# rocket_main_micro.net
KiCad netlist of a schematic drawn in Altium Designer
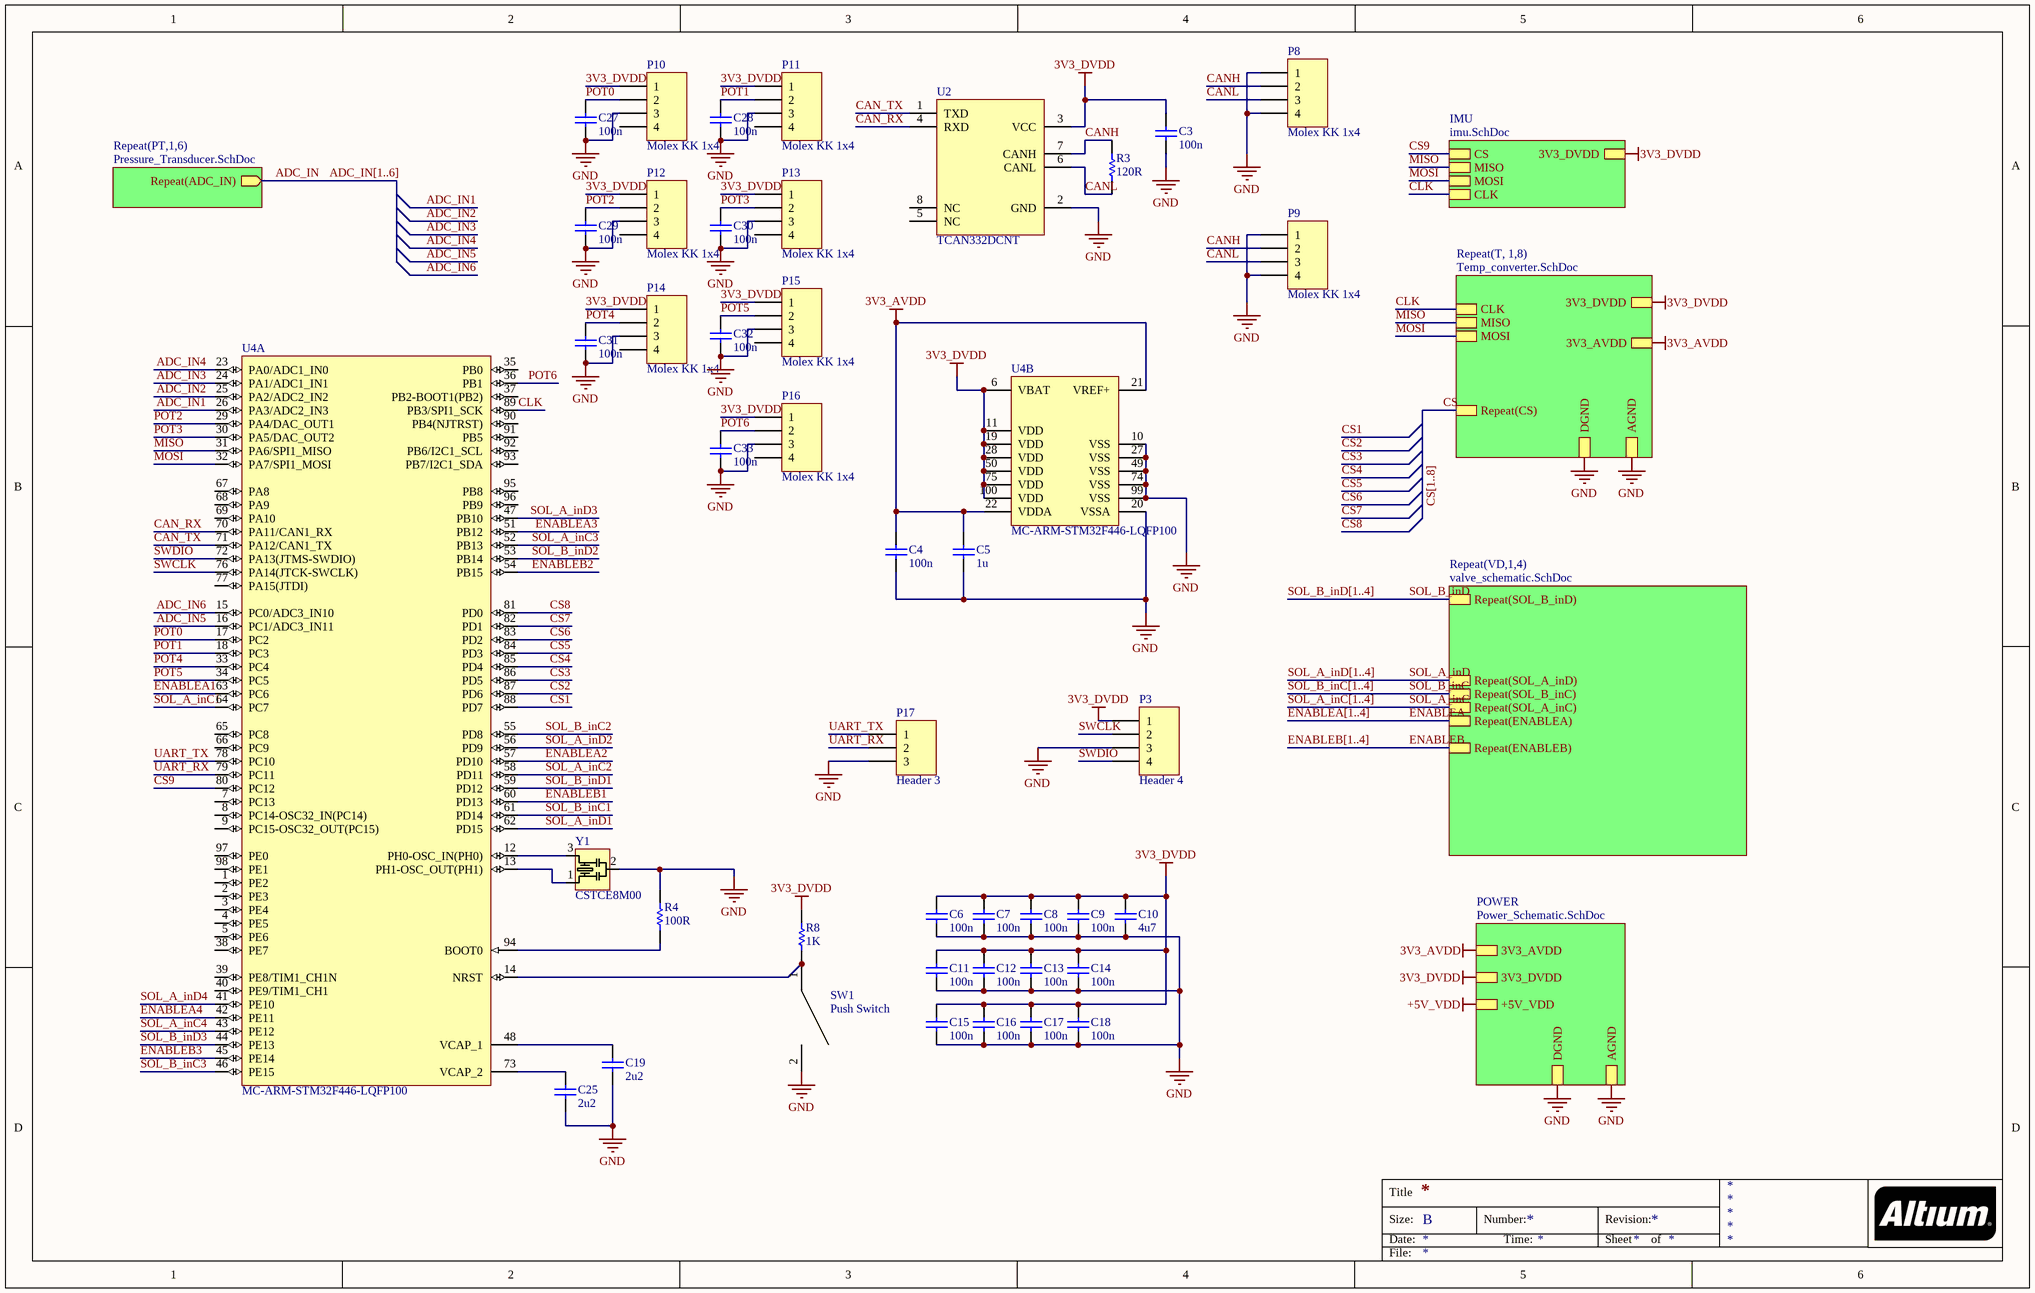
[diagram p0: rocket_main_micro.SchDoc]

(export (version "E")
  (design (tool "Eeschema 10.0.6"))
  (components
    (comp (ref "C3")
      (value "100n")
      (footprint "C0805")
      (description "0805 Capacitor")
      (libsource (lib "PARSEC") (part "C0805"))
    )
    (comp (ref "C4")
      (value "100n")
      (footprint "C0805")
      (description "0805 Capacitor")
      (libsource (lib "PARSEC1") (part "C0805"))
    )
    (comp (ref "C5")
      (value "1u")
      (footprint "C0805")
      (description "0805 Capacitor")
      (libsource (lib "PARSEC1") (part "C0805"))
    )
    (comp (ref "C6")
      (value "100n")
      (footprint "C0805")
      (description "0805 Capacitor")
      (libsource (lib "PARSEC1") (part "C0805"))
    )
    (comp (ref "C7")
      (value "100n")
      (footprint "C0805")
      (description "0805 Capacitor")
      (libsource (lib "PARSEC1") (part "C0805"))
    )
    (comp (ref "C8")
      (value "100n")
      (footprint "C0805")
      (description "0805 Capacitor")
      (libsource (lib "PARSEC1") (part "C0805"))
    )
    (comp (ref "C9")
      (value "100n")
      (footprint "C0805")
      (description "0805 Capacitor")
      (libsource (lib "PARSEC1") (part "C0805"))
    )
    (comp (ref "C10")
      (value "4u7")
      (footprint "C0805")
      (description "0805 Capacitor")
      (libsource (lib "PARSEC1") (part "C0805"))
    )
    (comp (ref "C11")
      (value "100n")
      (footprint "C0805")
      (description "0805 Capacitor")
      (libsource (lib "PARSEC1") (part "C0805"))
    )
    (comp (ref "C12")
      (value "100n")
      (footprint "C0805")
      (description "0805 Capacitor")
      (libsource (lib "PARSEC1") (part "C0805"))
    )
    (comp (ref "C13")
      (value "100n")
      (footprint "C0805")
      (description "0805 Capacitor")
      (libsource (lib "PARSEC1") (part "C0805"))
    )
    (comp (ref "C14")
      (value "100n")
      (footprint "C0805")
      (description "0805 Capacitor")
      (libsource (lib "PARSEC1") (part "C0805"))
    )
    (comp (ref "C15")
      (value "100n")
      (footprint "C0805")
      (description "0805 Capacitor")
      (libsource (lib "PARSEC1") (part "C0805"))
    )
    (comp (ref "C16")
      (value "100n")
      (footprint "C0805")
      (description "0805 Capacitor")
      (libsource (lib "PARSEC1") (part "C0805"))
    )
    (comp (ref "C17")
      (value "100n")
      (footprint "C0805")
      (description "0805 Capacitor")
      (libsource (lib "PARSEC1") (part "C0805"))
    )
    (comp (ref "C18")
      (value "100n")
      (footprint "C0805")
      (description "0805 Capacitor")
      (libsource (lib "PARSEC1") (part "C0805"))
    )
    (comp (ref "C19")
      (value "2u2")
      (footprint "C0805")
      (description "0805 Capacitor")
      (libsource (lib "PARSEC1") (part "C0805"))
    )
    (comp (ref "C25")
      (value "2u2")
      (footprint "C0805")
      (description "0805 Capacitor")
      (libsource (lib "PARSEC1") (part "C0805"))
    )
    (comp (ref "C27")
      (value "100n")
      (footprint "C0805")
      (description "0805 Capacitor")
      (libsource (lib "PARSEC1") (part "C0805"))
    )
    (comp (ref "C28")
      (value "100n")
      (footprint "C0805")
      (description "0805 Capacitor")
      (libsource (lib "PARSEC1") (part "C0805"))
    )
    (comp (ref "C29")
      (value "100n")
      (footprint "C0805")
      (description "0805 Capacitor")
      (libsource (lib "PARSEC1") (part "C0805"))
    )
    (comp (ref "C30")
      (value "100n")
      (footprint "C0805")
      (description "0805 Capacitor")
      (libsource (lib "PARSEC1") (part "C0805"))
    )
    (comp (ref "C31")
      (value "100n")
      (footprint "C0805")
      (description "0805 Capacitor")
      (libsource (lib "PARSEC1") (part "C0805"))
    )
    (comp (ref "C32")
      (value "100n")
      (footprint "C0805")
      (description "0805 Capacitor")
      (libsource (lib "PARSEC1") (part "C0805"))
    )
    (comp (ref "C33")
      (value "100n")
      (footprint "C0805")
      (description "0805 Capacitor")
      (libsource (lib "PARSEC1") (part "C0805"))
    )
    (comp (ref "P3")
      (value "Header 4")
      (footprint "HDR1X4")
      (description "Header, 4-Pin")
      (fields (field (name "PUBLISHER") "Altium Limited"))
      (libsource (lib "Miscellaneous Connectors") (part "Header 4"))
    )
    (comp (ref "P8")
      (value "Molex KK 1x4")
      (footprint "Molex KK 4x1")
      (description "1x4 Molex KK Connector")
      (libsource (lib "PARSEC") (part "Molex KK 1x4"))
    )
    (comp (ref "P9")
      (value "Molex KK 1x4")
      (footprint "Molex KK 4x1")
      (description "1x4 Molex KK Connector")
      (libsource (lib "PARSEC") (part "Molex KK 1x4"))
    )
    (comp (ref "P10")
      (value "Molex KK 1x4")
      (footprint "Molex KK 4x1")
      (description "1x4 Molex KK Connector")
      (libsource (lib "PARSEC") (part "Molex KK 1x4"))
    )
    (comp (ref "P11")
      (value "Molex KK 1x4")
      (footprint "Molex KK 4x1")
      (description "1x4 Molex KK Connector")
      (libsource (lib "PARSEC") (part "Molex KK 1x4"))
    )
    (comp (ref "P12")
      (value "Molex KK 1x4")
      (footprint "Molex KK 4x1")
      (description "1x4 Molex KK Connector")
      (libsource (lib "PARSEC") (part "Molex KK 1x4"))
    )
    (comp (ref "P13")
      (value "Molex KK 1x4")
      (footprint "Molex KK 4x1")
      (description "1x4 Molex KK Connector")
      (libsource (lib "PARSEC") (part "Molex KK 1x4"))
    )
    (comp (ref "P14")
      (value "Molex KK 1x4")
      (footprint "Molex KK 4x1")
      (description "1x4 Molex KK Connector")
      (libsource (lib "PARSEC") (part "Molex KK 1x4"))
    )
    (comp (ref "P15")
      (value "Molex KK 1x4")
      (footprint "Molex KK 4x1")
      (description "1x4 Molex KK Connector")
      (libsource (lib "PARSEC") (part "Molex KK 1x4"))
    )
    (comp (ref "P16")
      (value "Molex KK 1x4")
      (footprint "Molex KK 4x1")
      (description "1x4 Molex KK Connector")
      (libsource (lib "PARSEC") (part "Molex KK 1x4"))
    )
    (comp (ref "P17")
      (value "Header 3")
      (footprint "HDR1X3")
      (description "Header, 3-Pin")
      (fields (field (name "PUBLISHER") "Altium Limited"))
      (libsource (lib "Miscellaneous Connectors") (part "Header 3"))
    )
    (comp (ref "R3")
      (value "120R")
      (footprint "R0805")
      (description "RESISTOR 0805")
      (libsource (lib "PARSEC") (part "R0805"))
    )
    (comp (ref "R4")
      (value "100R")
      (footprint "R0805")
      (description "RESISTOR 0805")
      (libsource (lib "PARSEC1") (part "R0805"))
    )
    (comp (ref "R8")
      (value "1K")
      (footprint "R0805")
      (description "RESISTOR 0805")
      (libsource (lib "PARSEC1") (part "R0805"))
    )
    (comp (ref "SW1")
      (value "Push Switch")
      (footprint "PUSHBUTTON")
      (libsource (lib "PARSEC") (part "PUSHBUTTON"))
    )
    (comp (ref "U2")
      (value "TCAN332DCNT")
      (footprint "SOT-23-8")
      (description "IC TXRX CAN 3.3V SOT23-8")
      (libsource (lib "PARSEC") (part "TCAN332DCNT"))
    )
    (comp (ref "U4")
      (value "MC-ARM-STM32F446-LQFP100")
      (footprint "STM-LQFP100_N")
      (libsource (lib "PARSEC1") (part "MC-ARM-STM32F446-LQFP100"))
    )
    (comp (ref "Y1")
      (value "CSTCE8M00")
      (footprint "8MHz Ceramic Resonator")
      (description "8MHz Ceramic Resonator")
      (libsource (lib "PARSEC1") (part "CSTCE8M00"))
    )
  )
  (nets
    (net (code "6") (name "/ADC_IN1") (class "Default")
      (node (ref "U4") (pin "26") (pinfunction "PA3/ADC2_IN3_26") (pintype "bidirectional"))
    )
    (net (code "7") (name "/ADC_IN2") (class "Default")
      (node (ref "U4") (pin "25") (pinfunction "PA2/ADC2_IN2_25") (pintype "bidirectional"))
    )
    (net (code "8") (name "/ADC_IN3") (class "Default")
      (node (ref "U4") (pin "24") (pinfunction "PA1/ADC1_IN1_24") (pintype "bidirectional"))
    )
    (net (code "9") (name "/ADC_IN4") (class "Default")
      (node (ref "U4") (pin "23") (pinfunction "PA0/ADC1_IN0_23") (pintype "bidirectional"))
    )
    (net (code "10") (name "/ADC_IN5") (class "Default")
      (node (ref "U4") (pin "16") (pinfunction "PC1/ADC3_IN11_16") (pintype "bidirectional"))
    )
    (net (code "11") (name "/ADC_IN6") (class "Default")
      (node (ref "U4") (pin "15") (pinfunction "PC0/ADC3_IN10_15") (pintype "bidirectional"))
    )
    (net (code "13") (name "/CANH") (class "Default")
      (node (ref "P8") (pin "2") (pinfunction "2_2") (pintype "passive"))
      (node (ref "P9") (pin "2") (pinfunction "2_2") (pintype "passive"))
      (node (ref "R3") (pin "2") (pinfunction "2_2") (pintype "passive"))
      (node (ref "U2") (pin "7") (pinfunction "CANH_7") (pintype "passive"))
    )
    (net (code "14") (name "/CANL") (class "Default")
      (node (ref "P8") (pin "3") (pinfunction "3_3") (pintype "passive"))
      (node (ref "P9") (pin "3") (pinfunction "3_3") (pintype "passive"))
      (node (ref "R3") (pin "1") (pinfunction "1_1") (pintype "passive"))
      (node (ref "U2") (pin "6") (pinfunction "CANL_6") (pintype "passive"))
    )
    (net (code "15") (name "/CAN_RX") (class "Default")
      (node (ref "U2") (pin "4") (pinfunction "RXD_4") (pintype "passive"))
      (node (ref "U4") (pin "70") (pinfunction "PA11/CAN1_RX_70") (pintype "bidirectional"))
    )
    (net (code "16") (name "/CAN_TX") (class "Default")
      (node (ref "U2") (pin "1") (pinfunction "TXD_1") (pintype "passive"))
      (node (ref "U4") (pin "71") (pinfunction "PA12/CAN1_TX_71") (pintype "bidirectional"))
    )
    (net (code "17") (name "/CLK") (class "Default")
      (node (ref "U4") (pin "89") (pinfunction "PB3/SPI1_SCK_89") (pintype "bidirectional"))
    )
    (net (code "18") (name "/CS1") (class "Default")
      (node (ref "U4") (pin "88") (pinfunction "PD7_88") (pintype "bidirectional"))
    )
    (net (code "19") (name "/CS2") (class "Default")
      (node (ref "U4") (pin "87") (pinfunction "PD6_87") (pintype "bidirectional"))
    )
    (net (code "20") (name "/CS3") (class "Default")
      (node (ref "U4") (pin "86") (pinfunction "PD5_86") (pintype "bidirectional"))
    )
    (net (code "21") (name "/CS4") (class "Default")
      (node (ref "U4") (pin "85") (pinfunction "PD4_85") (pintype "bidirectional"))
    )
    (net (code "22") (name "/CS5") (class "Default")
      (node (ref "U4") (pin "84") (pinfunction "PD3_84") (pintype "bidirectional"))
    )
    (net (code "23") (name "/CS6") (class "Default")
      (node (ref "U4") (pin "83") (pinfunction "PD2_83") (pintype "bidirectional"))
    )
    (net (code "24") (name "/CS7") (class "Default")
      (node (ref "U4") (pin "82") (pinfunction "PD1_82") (pintype "bidirectional"))
    )
    (net (code "25") (name "/CS8") (class "Default")
      (node (ref "U4") (pin "81") (pinfunction "PD0_81") (pintype "bidirectional"))
    )
    (net (code "26") (name "/CS9") (class "Default")
      (node (ref "U4") (pin "80") (pinfunction "PC12_80") (pintype "bidirectional"))
    )
    (net (code "29") (name "/ENABLEA1") (class "Default")
      (node (ref "U4") (pin "63") (pinfunction "PC6_63") (pintype "bidirectional"))
    )
    (net (code "30") (name "/ENABLEA2") (class "Default")
      (node (ref "U4") (pin "57") (pinfunction "PD10_57") (pintype "bidirectional"))
    )
    (net (code "31") (name "/ENABLEA3") (class "Default")
      (node (ref "U4") (pin "51") (pinfunction "PB12_51") (pintype "bidirectional"))
    )
    (net (code "32") (name "/ENABLEA4") (class "Default")
      (node (ref "U4") (pin "42") (pinfunction "PE11_42") (pintype "bidirectional"))
    )
    (net (code "35") (name "/ENABLEB1") (class "Default")
      (node (ref "U4") (pin "60") (pinfunction "PD13_60") (pintype "bidirectional"))
    )
    (net (code "36") (name "/ENABLEB2") (class "Default")
      (node (ref "U4") (pin "54") (pinfunction "PB15_54") (pintype "bidirectional"))
    )
    (net (code "37") (name "/ENABLEB3") (class "Default")
      (node (ref "U4") (pin "45") (pinfunction "PE14_45") (pintype "bidirectional"))
    )
    (net (code "39") (name "/MISO") (class "Default")
      (node (ref "U4") (pin "31") (pinfunction "PA6/SPI1_MISO_31") (pintype "bidirectional"))
    )
    (net (code "40") (name "/MOSI") (class "Default")
      (node (ref "U4") (pin "32") (pinfunction "PA7/SPI1_MOSI_32") (pintype "bidirectional"))
    )
    (net (code "41") (name "/POT0") (class "Default")
      (node (ref "C27") (pin "1") (pinfunction "1_1") (pintype "passive"))
      (node (ref "P10") (pin "2") (pinfunction "2_2") (pintype "passive"))
      (node (ref "U4") (pin "17") (pinfunction "PC2_17") (pintype "bidirectional"))
    )
    (net (code "42") (name "/POT1") (class "Default")
      (node (ref "C28") (pin "1") (pinfunction "1_1") (pintype "passive"))
      (node (ref "P11") (pin "2") (pinfunction "2_2") (pintype "passive"))
      (node (ref "U4") (pin "18") (pinfunction "PC3_18") (pintype "bidirectional"))
    )
    (net (code "43") (name "/POT2") (class "Default")
      (node (ref "C29") (pin "1") (pinfunction "1_1") (pintype "passive"))
      (node (ref "P12") (pin "2") (pinfunction "2_2") (pintype "passive"))
      (node (ref "U4") (pin "29") (pinfunction "PA4/DAC_OUT1_29") (pintype "bidirectional"))
    )
    (net (code "44") (name "/POT3") (class "Default")
      (node (ref "C30") (pin "1") (pinfunction "1_1") (pintype "passive"))
      (node (ref "P13") (pin "2") (pinfunction "2_2") (pintype "passive"))
      (node (ref "U4") (pin "30") (pinfunction "PA5/DAC_OUT2_30") (pintype "bidirectional"))
    )
    (net (code "45") (name "/POT4") (class "Default")
      (node (ref "C31") (pin "1") (pinfunction "1_1") (pintype "passive"))
      (node (ref "P14") (pin "2") (pinfunction "2_2") (pintype "passive"))
      (node (ref "U4") (pin "33") (pinfunction "PC4_33") (pintype "bidirectional"))
    )
    (net (code "46") (name "/POT5") (class "Default")
      (node (ref "C32") (pin "1") (pinfunction "1_1") (pintype "passive"))
      (node (ref "P15") (pin "2") (pinfunction "2_2") (pintype "passive"))
      (node (ref "U4") (pin "34") (pinfunction "PC5_34") (pintype "bidirectional"))
    )
    (net (code "47") (name "/POT6") (class "Default")
      (node (ref "C33") (pin "1") (pinfunction "1_1") (pintype "passive"))
      (node (ref "P16") (pin "2") (pinfunction "2_2") (pintype "passive"))
      (node (ref "U4") (pin "36") (pinfunction "PB1_36") (pintype "bidirectional"))
    )
    (net (code "49") (name "/SOL_A_inC1") (class "Default")
      (node (ref "U4") (pin "64") (pinfunction "PC7_64") (pintype "bidirectional"))
    )
    (net (code "50") (name "/SOL_A_inC2") (class "Default")
      (node (ref "U4") (pin "58") (pinfunction "PD11_58") (pintype "bidirectional"))
    )
    (net (code "51") (name "/SOL_A_inC3") (class "Default")
      (node (ref "U4") (pin "52") (pinfunction "PB13_52") (pintype "bidirectional"))
    )
    (net (code "52") (name "/SOL_A_inC4") (class "Default")
      (node (ref "U4") (pin "43") (pinfunction "PE12_43") (pintype "bidirectional"))
    )
    (net (code "55") (name "/SOL_A_inD1") (class "Default")
      (node (ref "U4") (pin "62") (pinfunction "PD15_62") (pintype "bidirectional"))
    )
    (net (code "56") (name "/SOL_A_inD2") (class "Default")
      (node (ref "U4") (pin "56") (pinfunction "PD9_56") (pintype "bidirectional"))
    )
    (net (code "57") (name "/SOL_A_inD3") (class "Default")
      (node (ref "U4") (pin "47") (pinfunction "PB10_47") (pintype "bidirectional"))
    )
    (net (code "58") (name "/SOL_A_inD4") (class "Default")
      (node (ref "U4") (pin "41") (pinfunction "PE10_41") (pintype "bidirectional"))
    )
    (net (code "61") (name "/SOL_B_inC1") (class "Default")
      (node (ref "U4") (pin "61") (pinfunction "PD14_61") (pintype "bidirectional"))
    )
    (net (code "62") (name "/SOL_B_inC2") (class "Default")
      (node (ref "U4") (pin "55") (pinfunction "PD8_55") (pintype "bidirectional"))
    )
    (net (code "63") (name "/SOL_B_inC3") (class "Default")
      (node (ref "U4") (pin "46") (pinfunction "PE15_46") (pintype "bidirectional"))
    )
    (net (code "66") (name "/SOL_B_inD1") (class "Default")
      (node (ref "U4") (pin "59") (pinfunction "PD12_59") (pintype "bidirectional"))
    )
    (net (code "67") (name "/SOL_B_inD2") (class "Default")
      (node (ref "U4") (pin "53") (pinfunction "PB14_53") (pintype "bidirectional"))
    )
    (net (code "68") (name "/SOL_B_inD3") (class "Default")
      (node (ref "U4") (pin "44") (pinfunction "PE13_44") (pintype "bidirectional"))
    )
    (net (code "70") (name "/SWCLK") (class "Default")
      (node (ref "P3") (pin "2") (pinfunction "2_2") (pintype "passive"))
      (node (ref "U4") (pin "76") (pinfunction "PA14(JTCK-SWCLK)_76") (pintype "bidirectional"))
    )
    (net (code "71") (name "/SWDIO") (class "Default")
      (node (ref "P3") (pin "4") (pinfunction "4_4") (pintype "passive"))
      (node (ref "U4") (pin "72") (pinfunction "PA13(JTMS-SWDIO)_72") (pintype "bidirectional"))
    )
    (net (code "72") (name "/UART_RX") (class "Default")
      (node (ref "P17") (pin "2") (pinfunction "2_2") (pintype "passive"))
      (node (ref "U4") (pin "79") (pinfunction "PC11_79") (pintype "bidirectional"))
    )
    (net (code "73") (name "/UART_TX") (class "Default")
      (node (ref "P17") (pin "1") (pinfunction "1_1") (pintype "passive"))
      (node (ref "U4") (pin "78") (pinfunction "PC10_78") (pintype "bidirectional"))
    )
    (net (code "74") (name "3V3_AVDD") (class "Default")
      (node (ref "C4") (pin "1") (pinfunction "1_1") (pintype "passive"))
      (node (ref "C5") (pin "1") (pinfunction "1_1") (pintype "passive"))
      (node (ref "U4") (pin "21") (pinfunction "VREF+_21") (pintype "power_in"))
      (node (ref "U4") (pin "22") (pinfunction "VDDA_22") (pintype "power_in"))
    )
    (net (code "75") (name "3V3_DVDD") (class "Default")
      (node (ref "C10") (pin "1") (pinfunction "1_1") (pintype "passive"))
      (node (ref "C11") (pin "1") (pinfunction "1_1") (pintype "passive"))
      (node (ref "C12") (pin "1") (pinfunction "1_1") (pintype "passive"))
      (node (ref "C13") (pin "1") (pinfunction "1_1") (pintype "passive"))
      (node (ref "C14") (pin "1") (pinfunction "1_1") (pintype "passive"))
      (node (ref "C15") (pin "1") (pinfunction "1_1") (pintype "passive"))
      (node (ref "C16") (pin "1") (pinfunction "1_1") (pintype "passive"))
      (node (ref "C17") (pin "1") (pinfunction "1_1") (pintype "passive"))
      (node (ref "C18") (pin "1") (pinfunction "1_1") (pintype "passive"))
      (node (ref "C3") (pin "1") (pinfunction "1_1") (pintype "passive"))
      (node (ref "C6") (pin "1") (pinfunction "1_1") (pintype "passive"))
      (node (ref "C7") (pin "1") (pinfunction "1_1") (pintype "passive"))
      (node (ref "C8") (pin "1") (pinfunction "1_1") (pintype "passive"))
      (node (ref "C9") (pin "1") (pinfunction "1_1") (pintype "passive"))
      (node (ref "P10") (pin "1") (pinfunction "1_1") (pintype "passive"))
      (node (ref "P11") (pin "1") (pinfunction "1_1") (pintype "passive"))
      (node (ref "P12") (pin "1") (pinfunction "1_1") (pintype "passive"))
      (node (ref "P13") (pin "1") (pinfunction "1_1") (pintype "passive"))
      (node (ref "P14") (pin "1") (pinfunction "1_1") (pintype "passive"))
      (node (ref "P15") (pin "1") (pinfunction "1_1") (pintype "passive"))
      (node (ref "P16") (pin "1") (pinfunction "1_1") (pintype "passive"))
      (node (ref "P3") (pin "1") (pinfunction "1_1") (pintype "passive"))
      (node (ref "R8") (pin "2") (pinfunction "2_2") (pintype "passive"))
      (node (ref "U2") (pin "3") (pinfunction "VCC_3") (pintype "passive"))
      (node (ref "U4") (pin "100") (pinfunction "VDD_100") (pintype "power_in"))
      (node (ref "U4") (pin "11") (pinfunction "VDD_11") (pintype "power_in"))
      (node (ref "U4") (pin "19") (pinfunction "VDD_19") (pintype "power_in"))
      (node (ref "U4") (pin "28") (pinfunction "VDD_28") (pintype "power_in"))
      (node (ref "U4") (pin "50") (pinfunction "VDD_50") (pintype "power_in"))
      (node (ref "U4") (pin "6") (pinfunction "VBAT_6") (pintype "power_in"))
      (node (ref "U4") (pin "75") (pinfunction "VDD_75") (pintype "power_in"))
    )
    (net (code "76") (name "GND") (class "Default")
      (node (ref "C10") (pin "2") (pinfunction "2_2") (pintype "passive"))
      (node (ref "C11") (pin "2") (pinfunction "2_2") (pintype "passive"))
      (node (ref "C12") (pin "2") (pinfunction "2_2") (pintype "passive"))
      (node (ref "C13") (pin "2") (pinfunction "2_2") (pintype "passive"))
      (node (ref "C14") (pin "2") (pinfunction "2_2") (pintype "passive"))
      (node (ref "C15") (pin "2") (pinfunction "2_2") (pintype "passive"))
      (node (ref "C16") (pin "2") (pinfunction "2_2") (pintype "passive"))
      (node (ref "C17") (pin "2") (pinfunction "2_2") (pintype "passive"))
      (node (ref "C18") (pin "2") (pinfunction "2_2") (pintype "passive"))
      (node (ref "C19") (pin "2") (pinfunction "2_2") (pintype "passive"))
      (node (ref "C25") (pin "2") (pinfunction "2_2") (pintype "passive"))
      (node (ref "C27") (pin "2") (pinfunction "2_2") (pintype "passive"))
      (node (ref "C28") (pin "2") (pinfunction "2_2") (pintype "passive"))
      (node (ref "C29") (pin "2") (pinfunction "2_2") (pintype "passive"))
      (node (ref "C3") (pin "2") (pinfunction "2_2") (pintype "passive"))
      (node (ref "C30") (pin "2") (pinfunction "2_2") (pintype "passive"))
      (node (ref "C31") (pin "2") (pinfunction "2_2") (pintype "passive"))
      (node (ref "C32") (pin "2") (pinfunction "2_2") (pintype "passive"))
      (node (ref "C33") (pin "2") (pinfunction "2_2") (pintype "passive"))
      (node (ref "C4") (pin "2") (pinfunction "2_2") (pintype "passive"))
      (node (ref "C5") (pin "2") (pinfunction "2_2") (pintype "passive"))
      (node (ref "C6") (pin "2") (pinfunction "2_2") (pintype "passive"))
      (node (ref "C7") (pin "2") (pinfunction "2_2") (pintype "passive"))
      (node (ref "C8") (pin "2") (pinfunction "2_2") (pintype "passive"))
      (node (ref "C9") (pin "2") (pinfunction "2_2") (pintype "passive"))
      (node (ref "P10") (pin "3") (pinfunction "3_3") (pintype "passive"))
      (node (ref "P11") (pin "3") (pinfunction "3_3") (pintype "passive"))
      (node (ref "P12") (pin "3") (pinfunction "3_3") (pintype "passive"))
      (node (ref "P13") (pin "3") (pinfunction "3_3") (pintype "passive"))
      (node (ref "P14") (pin "3") (pinfunction "3_3") (pintype "passive"))
      (node (ref "P15") (pin "3") (pinfunction "3_3") (pintype "passive"))
      (node (ref "P16") (pin "3") (pinfunction "3_3") (pintype "passive"))
      (node (ref "P17") (pin "3") (pinfunction "3_3") (pintype "passive"))
      (node (ref "P3") (pin "3") (pinfunction "3_3") (pintype "passive"))
      (node (ref "P8") (pin "1") (pinfunction "1_1") (pintype "passive"))
      (node (ref "P8") (pin "4") (pinfunction "4_4") (pintype "passive"))
      (node (ref "P9") (pin "1") (pinfunction "1_1") (pintype "passive"))
      (node (ref "P9") (pin "4") (pinfunction "4_4") (pintype "passive"))
      (node (ref "R4") (pin "2") (pinfunction "2_2") (pintype "passive"))
      (node (ref "SW1") (pin "2") (pinfunction "3_2") (pintype "passive"))
      (node (ref "U2") (pin "2") (pinfunction "GND_2") (pintype "passive"))
      (node (ref "U4") (pin "10") (pinfunction "VSS_10") (pintype "power_in"))
      (node (ref "U4") (pin "20") (pinfunction "VSSA_20") (pintype "power_in"))
      (node (ref "U4") (pin "27") (pinfunction "VSS_27") (pintype "power_in"))
      (node (ref "U4") (pin "49") (pinfunction "VSS_49") (pintype "power_in"))
      (node (ref "U4") (pin "74") (pinfunction "VSS_74") (pintype "power_in"))
      (node (ref "U4") (pin "99") (pinfunction "VSS_99") (pintype "power_in"))
      (node (ref "Y1") (pin "2") (pinfunction "GND_2") (pintype "passive"))
    )
    (net (code "77") (name "Net-(SW1-2)") (class "Default")
      (node (ref "R8") (pin "1") (pinfunction "1_1") (pintype "passive"))
      (node (ref "SW1") (pin "1") (pinfunction "2_1") (pintype "passive"))
      (node (ref "U4") (pin "14") (pinfunction "NRST_14") (pintype "bidirectional"))
    )
    (net (code "78") (name "Net-(U4A-BOOT0)") (class "Default")
      (node (ref "R4") (pin "1") (pinfunction "1_1") (pintype "passive"))
      (node (ref "U4") (pin "94") (pinfunction "BOOT0_94") (pintype "input"))
    )
    (net (code "79") (name "Net-(U4A-PH0-OSC_IN(PH0))") (class "Default")
      (node (ref "U4") (pin "12") (pinfunction "PH0-OSC_IN(PH0)_12") (pintype "bidirectional"))
      (node (ref "Y1") (pin "3") (pinfunction "OSC2_3") (pintype "passive"))
    )
    (net (code "80") (name "Net-(U4A-PH1-OSC_OUT(PH1))") (class "Default")
      (node (ref "U4") (pin "13") (pinfunction "PH1-OSC_OUT(PH1)_13") (pintype "bidirectional"))
      (node (ref "Y1") (pin "1") (pinfunction "OSC1_1") (pintype "passive"))
    )
    (net (code "81") (name "Net-(U4A-VCAP_1)") (class "Default")
      (node (ref "C19") (pin "1") (pinfunction "1_1") (pintype "passive"))
      (node (ref "U4") (pin "48") (pinfunction "VCAP_1_48") (pintype "passive"))
    )
    (net (code "82") (name "Net-(U4A-VCAP_2)") (class "Default")
      (node (ref "C25") (pin "1") (pinfunction "1_1") (pintype "passive"))
      (node (ref "U4") (pin "73") (pinfunction "VCAP_2_73") (pintype "passive"))
    )
    (net (code "83") (name "unconnected-(P10-Pad4)") (class "Default")
      (node (ref "P10") (pin "4") (pinfunction "4_4") (pintype "passive"))
    )
    (net (code "84") (name "unconnected-(P11-Pad4)") (class "Default")
      (node (ref "P11") (pin "4") (pinfunction "4_4") (pintype "passive"))
    )
    (net (code "85") (name "unconnected-(P12-Pad4)") (class "Default")
      (node (ref "P12") (pin "4") (pinfunction "4_4") (pintype "passive"))
    )
    (net (code "86") (name "unconnected-(P13-Pad4)") (class "Default")
      (node (ref "P13") (pin "4") (pinfunction "4_4") (pintype "passive"))
    )
    (net (code "87") (name "unconnected-(P14-Pad4)") (class "Default")
      (node (ref "P14") (pin "4") (pinfunction "4_4") (pintype "passive"))
    )
    (net (code "88") (name "unconnected-(P15-Pad4)") (class "Default")
      (node (ref "P15") (pin "4") (pinfunction "4_4") (pintype "passive"))
    )
    (net (code "89") (name "unconnected-(P16-Pad4)") (class "Default")
      (node (ref "P16") (pin "4") (pinfunction "4_4") (pintype "passive"))
    )
    (net (code "90") (name "unconnected-(U2-NC-Pad5)") (class "Default")
      (node (ref "U2") (pin "5") (pinfunction "NC_5") (pintype "passive"))
    )
    (net (code "91") (name "unconnected-(U2-NC-Pad8)") (class "Default")
      (node (ref "U2") (pin "8") (pinfunction "NC_8") (pintype "passive"))
    )
    (net (code "92") (name "unconnected-(U4A-PA8-Pad67)") (class "Default")
      (node (ref "U4") (pin "67") (pinfunction "PA8_67") (pintype "bidirectional"))
    )
    (net (code "93") (name "unconnected-(U4A-PA9-Pad68)") (class "Default")
      (node (ref "U4") (pin "68") (pinfunction "PA9_68") (pintype "bidirectional"))
    )
    (net (code "94") (name "unconnected-(U4A-PA10-Pad69)") (class "Default")
      (node (ref "U4") (pin "69") (pinfunction "PA10_69") (pintype "bidirectional"))
    )
    (net (code "95") (name "unconnected-(U4A-PA15(JTDI)-Pad77)") (class "Default")
      (node (ref "U4") (pin "77") (pinfunction "PA15(JTDI)_77") (pintype "bidirectional"))
    )
    (net (code "96") (name "unconnected-(U4A-PB0-Pad35)") (class "Default")
      (node (ref "U4") (pin "35") (pinfunction "PB0_35") (pintype "bidirectional"))
    )
    (net (code "97") (name "unconnected-(U4A-PB2-BOOT1(PB2)-Pad37)") (class "Default")
      (node (ref "U4") (pin "37") (pinfunction "PB2-BOOT1(PB2)_37") (pintype "bidirectional"))
    )
    (net (code "98") (name "unconnected-(U4A-PB4(NJTRST)-Pad90)") (class "Default")
      (node (ref "U4") (pin "90") (pinfunction "PB4(NJTRST)_90") (pintype "bidirectional"))
    )
    (net (code "99") (name "unconnected-(U4A-PB5-Pad91)") (class "Default")
      (node (ref "U4") (pin "91") (pinfunction "PB5_91") (pintype "bidirectional"))
    )
    (net (code "100") (name "unconnected-(U4A-PB6{slash}I2C1_SCL-Pad92)") (class "Default")
      (node (ref "U4") (pin "92") (pinfunction "PB6/I2C1_SCL_92") (pintype "bidirectional"))
    )
    (net (code "101") (name "unconnected-(U4A-PB7{slash}I2C1_SDA-Pad93)") (class "Default")
      (node (ref "U4") (pin "93") (pinfunction "PB7/I2C1_SDA_93") (pintype "bidirectional"))
    )
    (net (code "102") (name "unconnected-(U4A-PB8-Pad95)") (class "Default")
      (node (ref "U4") (pin "95") (pinfunction "PB8_95") (pintype "bidirectional"))
    )
    (net (code "103") (name "unconnected-(U4A-PB9-Pad96)") (class "Default")
      (node (ref "U4") (pin "96") (pinfunction "PB9_96") (pintype "bidirectional"))
    )
    (net (code "104") (name "unconnected-(U4A-PC8-Pad65)") (class "Default")
      (node (ref "U4") (pin "65") (pinfunction "PC8_65") (pintype "bidirectional"))
    )
    (net (code "105") (name "unconnected-(U4A-PC9-Pad66)") (class "Default")
      (node (ref "U4") (pin "66") (pinfunction "PC9_66") (pintype "bidirectional"))
    )
    (net (code "106") (name "unconnected-(U4A-PC13-Pad7)") (class "Default")
      (node (ref "U4") (pin "7") (pinfunction "PC13_7") (pintype "bidirectional"))
    )
    (net (code "107") (name "unconnected-(U4A-PC14-OSC32_IN(PC14)-Pad8)") (class "Default")
      (node (ref "U4") (pin "8") (pinfunction "PC14-OSC32_IN(PC14)_8") (pintype "bidirectional"))
    )
    (net (code "108") (name "unconnected-(U4A-PC15-OSC32_OUT(PC15)-Pad9)") (class "Default")
      (node (ref "U4") (pin "9") (pinfunction "PC15-OSC32_OUT(PC15)_9") (pintype "bidirectional"))
    )
    (net (code "109") (name "unconnected-(U4A-PE0-Pad97)") (class "Default")
      (node (ref "U4") (pin "97") (pinfunction "PE0_97") (pintype "bidirectional"))
    )
    (net (code "110") (name "unconnected-(U4A-PE1-Pad98)") (class "Default")
      (node (ref "U4") (pin "98") (pinfunction "PE1_98") (pintype "bidirectional"))
    )
    (net (code "111") (name "unconnected-(U4A-PE2-Pad1)") (class "Default")
      (node (ref "U4") (pin "1") (pinfunction "PE2_1") (pintype "bidirectional"))
    )
    (net (code "112") (name "unconnected-(U4A-PE3-Pad2)") (class "Default")
      (node (ref "U4") (pin "2") (pinfunction "PE3_2") (pintype "bidirectional"))
    )
    (net (code "113") (name "unconnected-(U4A-PE4-Pad3)") (class "Default")
      (node (ref "U4") (pin "3") (pinfunction "PE4_3") (pintype "bidirectional"))
    )
    (net (code "114") (name "unconnected-(U4A-PE5-Pad4)") (class "Default")
      (node (ref "U4") (pin "4") (pinfunction "PE5_4") (pintype "bidirectional"))
    )
    (net (code "115") (name "unconnected-(U4A-PE6-Pad5)") (class "Default")
      (node (ref "U4") (pin "5") (pinfunction "PE6_5") (pintype "bidirectional"))
    )
    (net (code "116") (name "unconnected-(U4A-PE7-Pad38)") (class "Default")
      (node (ref "U4") (pin "38") (pinfunction "PE7_38") (pintype "bidirectional"))
    )
    (net (code "117") (name "unconnected-(U4A-PE8{slash}TIM1_CH1N-Pad39)") (class "Default")
      (node (ref "U4") (pin "39") (pinfunction "PE8/TIM1_CH1N_39") (pintype "bidirectional"))
    )
    (net (code "118") (name "unconnected-(U4A-PE9{slash}TIM1_CH1-Pad40)") (class "Default")
      (node (ref "U4") (pin "40") (pinfunction "PE9/TIM1_CH1_40") (pintype "bidirectional"))
    )
  )
)
